# POWER.net
KiCad netlist of a schematic drawn in Altium Designer
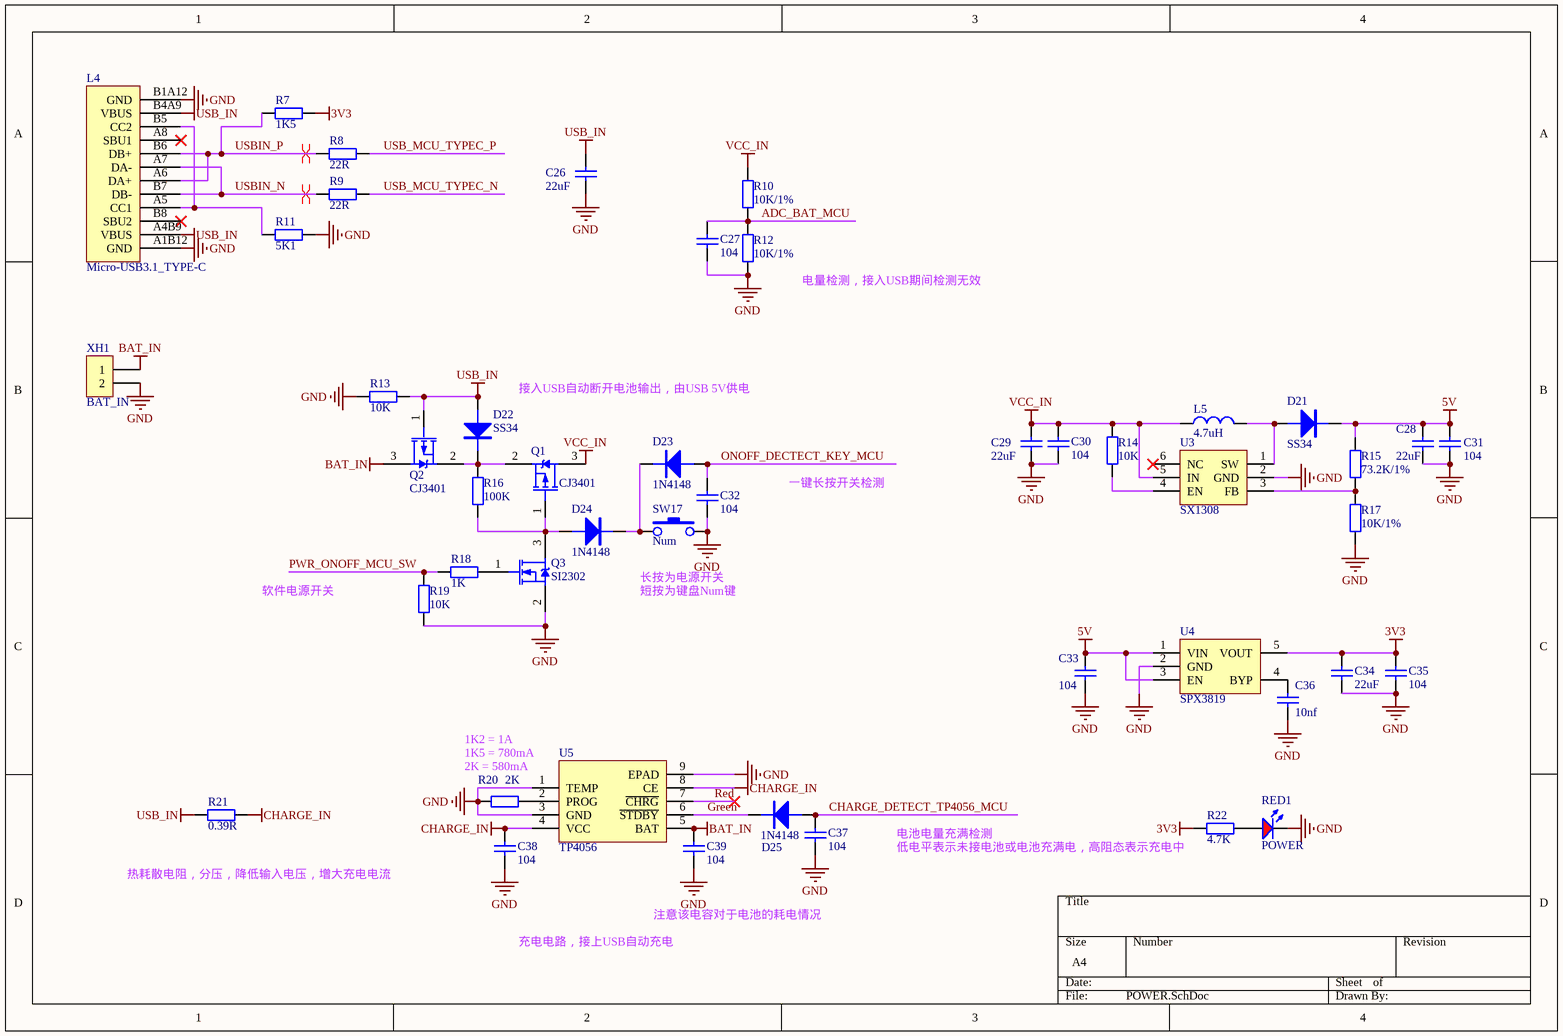
[diagram p0: POWER.SchDoc]

(export (version "E")
  (design (tool "Eeschema 10.0.6"))
  (components
    (comp (ref "C26")
      (value "22uF")
      (footprint "Cap-0805")
      (description "贴片陶瓷电容")
      (libsource (lib "Miscellaneous Base") (part "CAP"))
    )
    (comp (ref "C27")
      (value "104")
      (footprint "Cap-0603")
      (description "贴片陶瓷电容")
      (libsource (lib "Miscellaneous Base") (part "CAP"))
    )
    (comp (ref "C28")
      (value "22uF")
      (footprint "Cap-0805")
      (description "贴片陶瓷电容")
      (libsource (lib "Miscellaneous Base") (part "CAP"))
    )
    (comp (ref "C29")
      (value "22uF")
      (footprint "Cap-0805")
      (description "贴片陶瓷电容")
      (libsource (lib "Miscellaneous Base") (part "CAP"))
    )
    (comp (ref "C30")
      (value "104")
      (footprint "Cap-0603")
      (description "贴片陶瓷电容")
      (libsource (lib "Miscellaneous Base") (part "CAP"))
    )
    (comp (ref "C31")
      (value "104")
      (footprint "Cap-0603")
      (description "贴片陶瓷电容")
      (libsource (lib "Miscellaneous Base") (part "CAP"))
    )
    (comp (ref "C32")
      (value "104")
      (footprint "Cap-0603")
      (description "贴片陶瓷电容")
      (libsource (lib "Miscellaneous Base") (part "CAP"))
    )
    (comp (ref "C33")
      (value "104")
      (footprint "Cap-0603")
      (description "贴片陶瓷电容")
      (libsource (lib "Miscellaneous Base") (part "CAP"))
    )
    (comp (ref "C34")
      (value "22uF")
      (footprint "Cap-0805")
      (description "贴片陶瓷电容")
      (libsource (lib "Miscellaneous Base") (part "CAP"))
    )
    (comp (ref "C35")
      (value "104")
      (footprint "Cap-0603")
      (description "贴片陶瓷电容")
      (libsource (lib "Miscellaneous Base") (part "CAP"))
    )
    (comp (ref "C36") (value "10nf") (footprint "Cap-0603") (libsource (lib "base") (part "Cap")))
    (comp (ref "C37")
      (value "104")
      (footprint "Cap-0603")
      (description "贴片陶瓷电容")
      (libsource (lib "Miscellaneous Base") (part "CAP"))
    )
    (comp (ref "C38")
      (value "104")
      (footprint "Cap-0603")
      (description "贴片陶瓷电容")
      (libsource (lib "Miscellaneous Base") (part "CAP"))
    )
    (comp (ref "C39")
      (value "104")
      (footprint "Cap-0603")
      (description "贴片陶瓷电容")
      (libsource (lib "Miscellaneous Base") (part "CAP"))
    )
    (comp (ref "D21")
      (value "SS34")
      (footprint "Doide-SMA")
      (description "普通二极管")
      (libsource (lib "Miscellaneous Transistor") (part "DIODE"))
    )
    (comp (ref "D22")
      (value "SS34")
      (footprint "Doide-SMA")
      (description "普通二极管")
      (libsource (lib "Miscellaneous Transistor") (part "DIODE"))
    )
    (comp (ref "D23")
      (value "1N4148")
      (footprint "SOD-523")
      (description "普通二极管")
      (libsource (lib "Miscellaneous Transistor") (part "DIODE"))
    )
    (comp (ref "D24")
      (value "1N4148")
      (footprint "SOD-523")
      (description "普通二极管")
      (libsource (lib "Miscellaneous Transistor") (part "DIODE"))
    )
    (comp (ref "D25")
      (value "1N4148")
      (footprint "SOD-523")
      (description "普通二极管")
      (libsource (lib "Miscellaneous Transistor") (part "DIODE"))
    )
    (comp (ref "L4")
      (value "Micro-USB3.1_TYPE-C")
      (footprint "USB3.0-TYPEC-12P")
      (libsource (lib "Miscellaneous Socket") (part "Micro-USB3.1_TYPE-C"))
    )
    (comp (ref "L5")
      (value "4.7uH")
      (footprint "L-MHC0603")
      (description "贴片屏蔽电感")
      (libsource (lib "Miscellaneous Base") (part "INDUCTOR-SMD"))
    )
    (comp (ref "Q1")
      (value "CJ3401")
      (footprint "SOT23-3")
      (description "P-Channel MOSFET")
      (fields (field (name "PUBLISHER") "Altium Limited"))
      (libsource (lib "Miscellaneous Transistor") (part "MOSFET-P2"))
    )
    (comp (ref "Q2")
      (value "CJ3401")
      (footprint "SOT23-3")
      (description "P-Channel MOSFET")
      (fields (field (name "PUBLISHER") "Altium Limited"))
      (libsource (lib "Miscellaneous Transistor") (part "MOSFET-P2"))
    )
    (comp (ref "Q3")
      (value "SI2302")
      (footprint "SOT23-3")
      (description "N-Channel MOSFET")
      (fields (field (name "PUBLISHER") "Altium Limited"))
      (libsource (lib "Miscellaneous Transistor") (part "MOSFET-N2"))
    )
    (comp (ref "R7")
      (value "1K5")
      (footprint "Res-0603")
      (description "贴片电阻")
      (libsource (lib "") (part "RES_2"))
    )
    (comp (ref "R8")
      (value "22R")
      (footprint "Res-0603")
      (description "贴片电阻")
      (libsource (lib "") (part "RES_2"))
    )
    (comp (ref "R9")
      (value "22R")
      (footprint "Res-0603")
      (description "贴片电阻")
      (libsource (lib "") (part "RES_2"))
    )
    (comp (ref "R10")
      (value "10K/1%")
      (footprint "Res-0603")
      (description "贴片电阻")
      (libsource (lib "") (part "RES_3"))
    )
    (comp (ref "R11")
      (value "5K1")
      (footprint "Res-0603")
      (description "贴片电阻")
      (libsource (lib "") (part "RES_2"))
    )
    (comp (ref "R12")
      (value "10K/1%")
      (footprint "Res-0603")
      (description "贴片电阻")
      (libsource (lib "") (part "RES_3"))
    )
    (comp (ref "R13")
      (value "10K")
      (footprint "Res-0603")
      (description "贴片电阻")
      (libsource (lib "") (part "RES_2"))
    )
    (comp (ref "R14")
      (value "10K")
      (footprint "Res-0603")
      (description "贴片电阻")
      (libsource (lib "") (part "RES_2"))
    )
    (comp (ref "R15")
      (value "73.2K/1%")
      (footprint "Res-0603")
      (description "贴片电阻")
      (libsource (lib "Miscellaneous Base") (part "RES"))
    )
    (comp (ref "R16")
      (value "100K")
      (footprint "Res-0603")
      (description "贴片电阻")
      (libsource (lib "") (part "RES_1"))
    )
    (comp (ref "R17")
      (value "10K/1%")
      (footprint "Res-0603")
      (description "贴片电阻")
      (libsource (lib "Miscellaneous Base") (part "RES"))
    )
    (comp (ref "R18")
      (value "1K")
      (footprint "Res-0603")
      (description "贴片电阻")
      (libsource (lib "Miscellaneous Base") (part "RES"))
    )
    (comp (ref "R19")
      (value "10K")
      (footprint "Res-0603")
      (description "贴片电阻")
      (libsource (lib "") (part "RES_1"))
    )
    (comp (ref "R20")
      (value "2K")
      (footprint "Res-0603")
      (description "贴片电阻")
      (libsource (lib "") (part "RES_2"))
    )
    (comp (ref "R21")
      (value "0.39R")
      (footprint "Res-1812")
      (description "贴片电阻")
      (libsource (lib "Miscellaneous Base") (part "RES"))
    )
    (comp (ref "R22")
      (value "4.7K")
      (footprint "Res-0603")
      (description "贴片电阻")
      (libsource (lib "") (part "RES_2"))
    )
    (comp (ref "RED1")
      (value "POWER")
      (footprint "LED_0603_R")
      (description "发光二极管")
      (libsource (lib "Miscellaneous Transistor") (part "LED_SMD_RED"))
    )
    (comp (ref "SW17")
      (value "Num")
      (footprint "MX_SW-4")
      (description "with Fixation pins  1-Pole")
      (libsource (lib "KeyBoard_rebacha") (part "MX_SW-4"))
    )
    (comp (ref "U3")
      (value "SX1308")
      (footprint "SX1308")
      (libsource (lib "Miscellaneous PMIC") (part "SX1308"))
    )
    (comp (ref "U4")
      (value "SPX3819")
      (footprint "SOT23-5")
      (libsource (lib "Miscellaneous PMIC") (part "SPX3819"))
    )
    (comp (ref "U5")
      (value "TP4056")
      (footprint "TP4056")
      (libsource (lib "Miscellaneous PMIC") (part "tp4056"))
    )
    (comp (ref "XH1") (value "BAT_IN") (footprint "XH2/2.54mm/180") (libsource (lib "XH，VH") (part "XH2")))
  )
  (nets
    (net (code "1") (name "/ADC_BAT_MCU") (class "Default")
      (node (ref "C27") (pin "2") (pinfunction "2_2") (pintype "passive"))
      (node (ref "R10") (pin "1") (pinfunction "1_1") (pintype "passive"))
      (node (ref "R12") (pin "2") (pinfunction "2_2") (pintype "passive"))
    )
    (net (code "2") (name "/CHARGE_DETECT_TP4056_MCU") (class "Default")
      (node (ref "C37") (pin "2") (pinfunction "2_2") (pintype "passive"))
      (node (ref "D25") (pin "A") (pinfunction "A_A") (pintype "passive"))
    )
    (net (code "3") (name "/Green") (class "Default")
      (node (ref "D25") (pin "K") (pinfunction "K_K") (pintype "passive"))
      (node (ref "U5") (pin "6") (pinfunction "~{STDBY}_6") (pintype "passive"))
    )
    (net (code "4") (name "/ONOFF_DECTECT_KEY_MCU") (class "Default")
      (node (ref "C32") (pin "1") (pinfunction "1_1") (pintype "passive"))
      (node (ref "D23") (pin "A") (pinfunction "A_A") (pintype "passive"))
    )
    (net (code "5") (name "/PWR_ONOFF_MCU_SW") (class "Default")
      (node (ref "R18") (pin "1") (pinfunction "1_1") (pintype "passive"))
      (node (ref "R19") (pin "1") (pinfunction "1_1") (pintype "passive"))
    )
    (net (code "6") (name "/Red") (class "Default")
      (node (ref "U5") (pin "7") (pinfunction "~{CHRG}_7") (pintype "passive+no_connect"))
    )
    (net (code "7") (name "/USBIN_N") (class "Default")
      (node (ref "L4") (pin "A7") (pinfunction "DA-_A7") (pintype "passive"))
      (node (ref "L4") (pin "B7") (pinfunction "DB-_B7") (pintype "passive"))
      (node (ref "R9") (pin "2") (pinfunction "2_2") (pintype "passive"))
    )
    (net (code "8") (name "/USBIN_P") (class "Default")
      (node (ref "L4") (pin "A6") (pinfunction "DA+_A6") (pintype "passive"))
      (node (ref "L4") (pin "B6") (pinfunction "DB+_B6") (pintype "passive"))
      (node (ref "R7") (pin "2") (pinfunction "2_2") (pintype "passive"))
      (node (ref "R8") (pin "2") (pinfunction "2_2") (pintype "passive"))
    )
    (net (code "9") (name "/USB_MCU_TYPEC_N") (class "Default")
      (node (ref "R9") (pin "1") (pinfunction "1_1") (pintype "passive"))
    )
    (net (code "10") (name "/USB_MCU_TYPEC_P") (class "Default")
      (node (ref "R8") (pin "1") (pinfunction "1_1") (pintype "passive"))
    )
    (net (code "11") (name "3V3") (class "Default")
      (node (ref "C34") (pin "2") (pinfunction "2_2") (pintype "passive"))
      (node (ref "C35") (pin "1") (pinfunction "1_1") (pintype "passive"))
      (node (ref "R22") (pin "2") (pinfunction "2_2") (pintype "passive"))
      (node (ref "R7") (pin "1") (pinfunction "1_1") (pintype "passive"))
      (node (ref "U4") (pin "5") (pinfunction "VOUT_5") (pintype "power_in"))
    )
    (net (code "12") (name "5V") (class "Default")
      (node (ref "C28") (pin "2") (pinfunction "2_2") (pintype "passive"))
      (node (ref "C31") (pin "2") (pinfunction "2_2") (pintype "passive"))
      (node (ref "C33") (pin "2") (pinfunction "2_2") (pintype "passive"))
      (node (ref "D21") (pin "K") (pinfunction "K_K") (pintype "passive"))
      (node (ref "R15") (pin "2") (pinfunction "2_2") (pintype "passive"))
      (node (ref "U4") (pin "1") (pinfunction "VIN_1") (pintype "power_in"))
      (node (ref "U4") (pin "3") (pinfunction "EN_3") (pintype "power_in"))
    )
    (net (code "13") (name "BAT_IN") (class "Default")
      (node (ref "C39") (pin "2") (pinfunction "2_2") (pintype "passive"))
      (node (ref "Q2") (pin "3") (pinfunction "D_3") (pintype "passive"))
      (node (ref "U5") (pin "5") (pinfunction "BAT_5") (pintype "passive"))
      (node (ref "XH1") (pin "1") (pinfunction "1_1") (pintype "passive"))
    )
    (net (code "14") (name "CHARGE_IN") (class "Default")
      (node (ref "C38") (pin "2") (pinfunction "2_2") (pintype "passive"))
      (node (ref "R21") (pin "2") (pinfunction "2_2") (pintype "passive"))
      (node (ref "U5") (pin "4") (pinfunction "VCC_4") (pintype "passive"))
      (node (ref "U5") (pin "8") (pinfunction "CE_8") (pintype "passive"))
    )
    (net (code "15") (name "GND") (class "Default")
      (node (ref "C26") (pin "1") (pinfunction "1_1") (pintype "passive"))
      (node (ref "C27") (pin "1") (pinfunction "1_1") (pintype "passive"))
      (node (ref "C28") (pin "1") (pinfunction "1_1") (pintype "passive"))
      (node (ref "C29") (pin "1") (pinfunction "1_1") (pintype "passive"))
      (node (ref "C30") (pin "1") (pinfunction "1_1") (pintype "passive"))
      (node (ref "C31") (pin "1") (pinfunction "1_1") (pintype "passive"))
      (node (ref "C32") (pin "2") (pinfunction "2_2") (pintype "passive"))
      (node (ref "C33") (pin "1") (pinfunction "1_1") (pintype "passive"))
      (node (ref "C34") (pin "1") (pinfunction "1_1") (pintype "passive"))
      (node (ref "C35") (pin "2") (pinfunction "2_2") (pintype "passive"))
      (node (ref "C36") (pin "1") (pinfunction "1_1") (pintype "passive"))
      (node (ref "C37") (pin "1") (pinfunction "1_1") (pintype "passive"))
      (node (ref "C38") (pin "1") (pinfunction "1_1") (pintype "passive"))
      (node (ref "C39") (pin "1") (pinfunction "1_1") (pintype "passive"))
      (node (ref "L4") (pin "A1B12") (pinfunction "GND_A1B12") (pintype "passive"))
      (node (ref "L4") (pin "B1A12") (pinfunction "GND_B1A12") (pintype "passive"))
      (node (ref "Q3") (pin "2") (pinfunction "S_2") (pintype "passive"))
      (node (ref "R11") (pin "1") (pinfunction "1_1") (pintype "passive"))
      (node (ref "R12") (pin "1") (pinfunction "1_1") (pintype "passive"))
      (node (ref "R13") (pin "2") (pinfunction "2_2") (pintype "passive"))
      (node (ref "R17") (pin "1") (pinfunction "1_1") (pintype "passive"))
      (node (ref "R19") (pin "2") (pinfunction "2_2") (pintype "passive"))
      (node (ref "R20") (pin "2") (pinfunction "2_2") (pintype "passive"))
      (node (ref "RED1") (pin "2") (pinfunction "K_2") (pintype "passive"))
      (node (ref "SW17") (pin "2") (pinfunction "2_2") (pintype "passive"))
      (node (ref "U3") (pin "2") (pinfunction "GND_2") (pintype "passive"))
      (node (ref "U4") (pin "2") (pinfunction "GND_2") (pintype "power_in"))
      (node (ref "U5") (pin "1") (pinfunction "TEMP_1") (pintype "passive"))
      (node (ref "U5") (pin "3") (pinfunction "GND_3") (pintype "passive"))
      (node (ref "U5") (pin "9") (pinfunction "EPAD_9") (pintype "passive"))
      (node (ref "XH1") (pin "2") (pinfunction "2_2") (pintype "passive"))
    )
    (net (code "16") (name "Net-(D23-PadK)") (class "Default")
      (node (ref "D23") (pin "K") (pinfunction "K_K") (pintype "passive"))
      (node (ref "D24") (pin "K") (pinfunction "K_K") (pintype "passive"))
      (node (ref "SW17") (pin "1") (pinfunction "1_1") (pintype "passive"))
    )
    (net (code "17") (name "Net-(L4-CC1)") (class "Default")
      (node (ref "L4") (pin "A5") (pinfunction "CC1_A5") (pintype "passive"))
      (node (ref "L4") (pin "B5") (pinfunction "CC2_B5") (pintype "passive"))
      (node (ref "R11") (pin "2") (pinfunction "2_2") (pintype "passive"))
    )
    (net (code "18") (name "Net-(Q1-G)") (class "Default")
      (node (ref "D24") (pin "A") (pinfunction "A_A") (pintype "passive"))
      (node (ref "Q1") (pin "1") (pinfunction "G_1") (pintype "passive"))
      (node (ref "Q3") (pin "3") (pinfunction "D_3") (pintype "passive"))
      (node (ref "R16") (pin "2") (pinfunction "2_2") (pintype "passive"))
    )
    (net (code "19") (name "Net-(Q1-S)") (class "Default")
      (node (ref "D22") (pin "K") (pinfunction "K_K") (pintype "passive"))
      (node (ref "Q1") (pin "2") (pinfunction "S_2") (pintype "passive"))
      (node (ref "Q2") (pin "2") (pinfunction "S_2") (pintype "passive"))
      (node (ref "R16") (pin "1") (pinfunction "1_1") (pintype "passive"))
    )
    (net (code "20") (name "Net-(Q3-G)") (class "Default")
      (node (ref "Q3") (pin "1") (pinfunction "G_1") (pintype "passive"))
      (node (ref "R18") (pin "2") (pinfunction "2_2") (pintype "passive"))
    )
    (net (code "21") (name "Net-(RED1-A)") (class "Default")
      (node (ref "R22") (pin "1") (pinfunction "1_1") (pintype "passive"))
      (node (ref "RED1") (pin "1") (pinfunction "A_1") (pintype "passive"))
    )
    (net (code "22") (name "Net-(U3-EN)") (class "Default")
      (node (ref "R14") (pin "2") (pinfunction "2_2") (pintype "passive"))
      (node (ref "U3") (pin "4") (pinfunction "EN_4") (pintype "passive"))
    )
    (net (code "23") (name "Net-(U3-FB)") (class "Default")
      (node (ref "R15") (pin "1") (pinfunction "1_1") (pintype "passive"))
      (node (ref "R17") (pin "2") (pinfunction "2_2") (pintype "passive"))
      (node (ref "U3") (pin "3") (pinfunction "FB_3") (pintype "passive"))
    )
    (net (code "24") (name "Net-(U3-SW)") (class "Default")
      (node (ref "D21") (pin "A") (pinfunction "A_A") (pintype "passive"))
      (node (ref "L5") (pin "1") (pinfunction "1_1") (pintype "passive"))
      (node (ref "U3") (pin "1") (pinfunction "SW_1") (pintype "passive"))
    )
    (net (code "25") (name "Net-(U4-BYP)") (class "Default")
      (node (ref "C36") (pin "2") (pinfunction "2_2") (pintype "passive"))
      (node (ref "U4") (pin "4") (pinfunction "BYP_4") (pintype "power_in"))
    )
    (net (code "26") (name "Net-(U5-PROG)") (class "Default")
      (node (ref "R20") (pin "1") (pinfunction "1_1") (pintype "passive"))
      (node (ref "U5") (pin "2") (pinfunction "PROG_2") (pintype "passive"))
    )
    (net (code "27") (name "USB_IN") (class "Default")
      (node (ref "C26") (pin "2") (pinfunction "2_2") (pintype "passive"))
      (node (ref "D22") (pin "A") (pinfunction "A_A") (pintype "passive"))
      (node (ref "L4") (pin "A4B9") (pinfunction "VBUS_A4B9") (pintype "passive"))
      (node (ref "L4") (pin "B4A9") (pinfunction "VBUS_B4A9") (pintype "passive"))
      (node (ref "Q2") (pin "1") (pinfunction "G_1") (pintype "passive"))
      (node (ref "R13") (pin "1") (pinfunction "1_1") (pintype "passive"))
      (node (ref "R21") (pin "1") (pinfunction "1_1") (pintype "passive"))
    )
    (net (code "28") (name "VCC_IN") (class "Default")
      (node (ref "C29") (pin "2") (pinfunction "2_2") (pintype "passive"))
      (node (ref "C30") (pin "2") (pinfunction "2_2") (pintype "passive"))
      (node (ref "L5") (pin "2") (pinfunction "2_2") (pintype "passive"))
      (node (ref "Q1") (pin "3") (pinfunction "D_3") (pintype "passive"))
      (node (ref "R10") (pin "2") (pinfunction "2_2") (pintype "passive"))
      (node (ref "R14") (pin "1") (pinfunction "1_1") (pintype "passive"))
      (node (ref "U3") (pin "5") (pinfunction "IN_5") (pintype "passive"))
    )
    (net (code "29") (name "unconnected-(L4-SBU1-PadA8)") (class "Default")
      (node (ref "L4") (pin "A8") (pinfunction "SBU1_A8") (pintype "passive+no_connect"))
    )
    (net (code "30") (name "unconnected-(L4-SBU2-PadB8)") (class "Default")
      (node (ref "L4") (pin "B8") (pinfunction "SBU2_B8") (pintype "passive+no_connect"))
    )
    (net (code "31") (name "unconnected-(U3-NC-Pad6)") (class "Default")
      (node (ref "U3") (pin "6") (pinfunction "NC_6") (pintype "passive+no_connect"))
    )
  )
)
